# avr_programming_shield_v2b.net
KiCad netlist of a schematic drawn in EAGLE
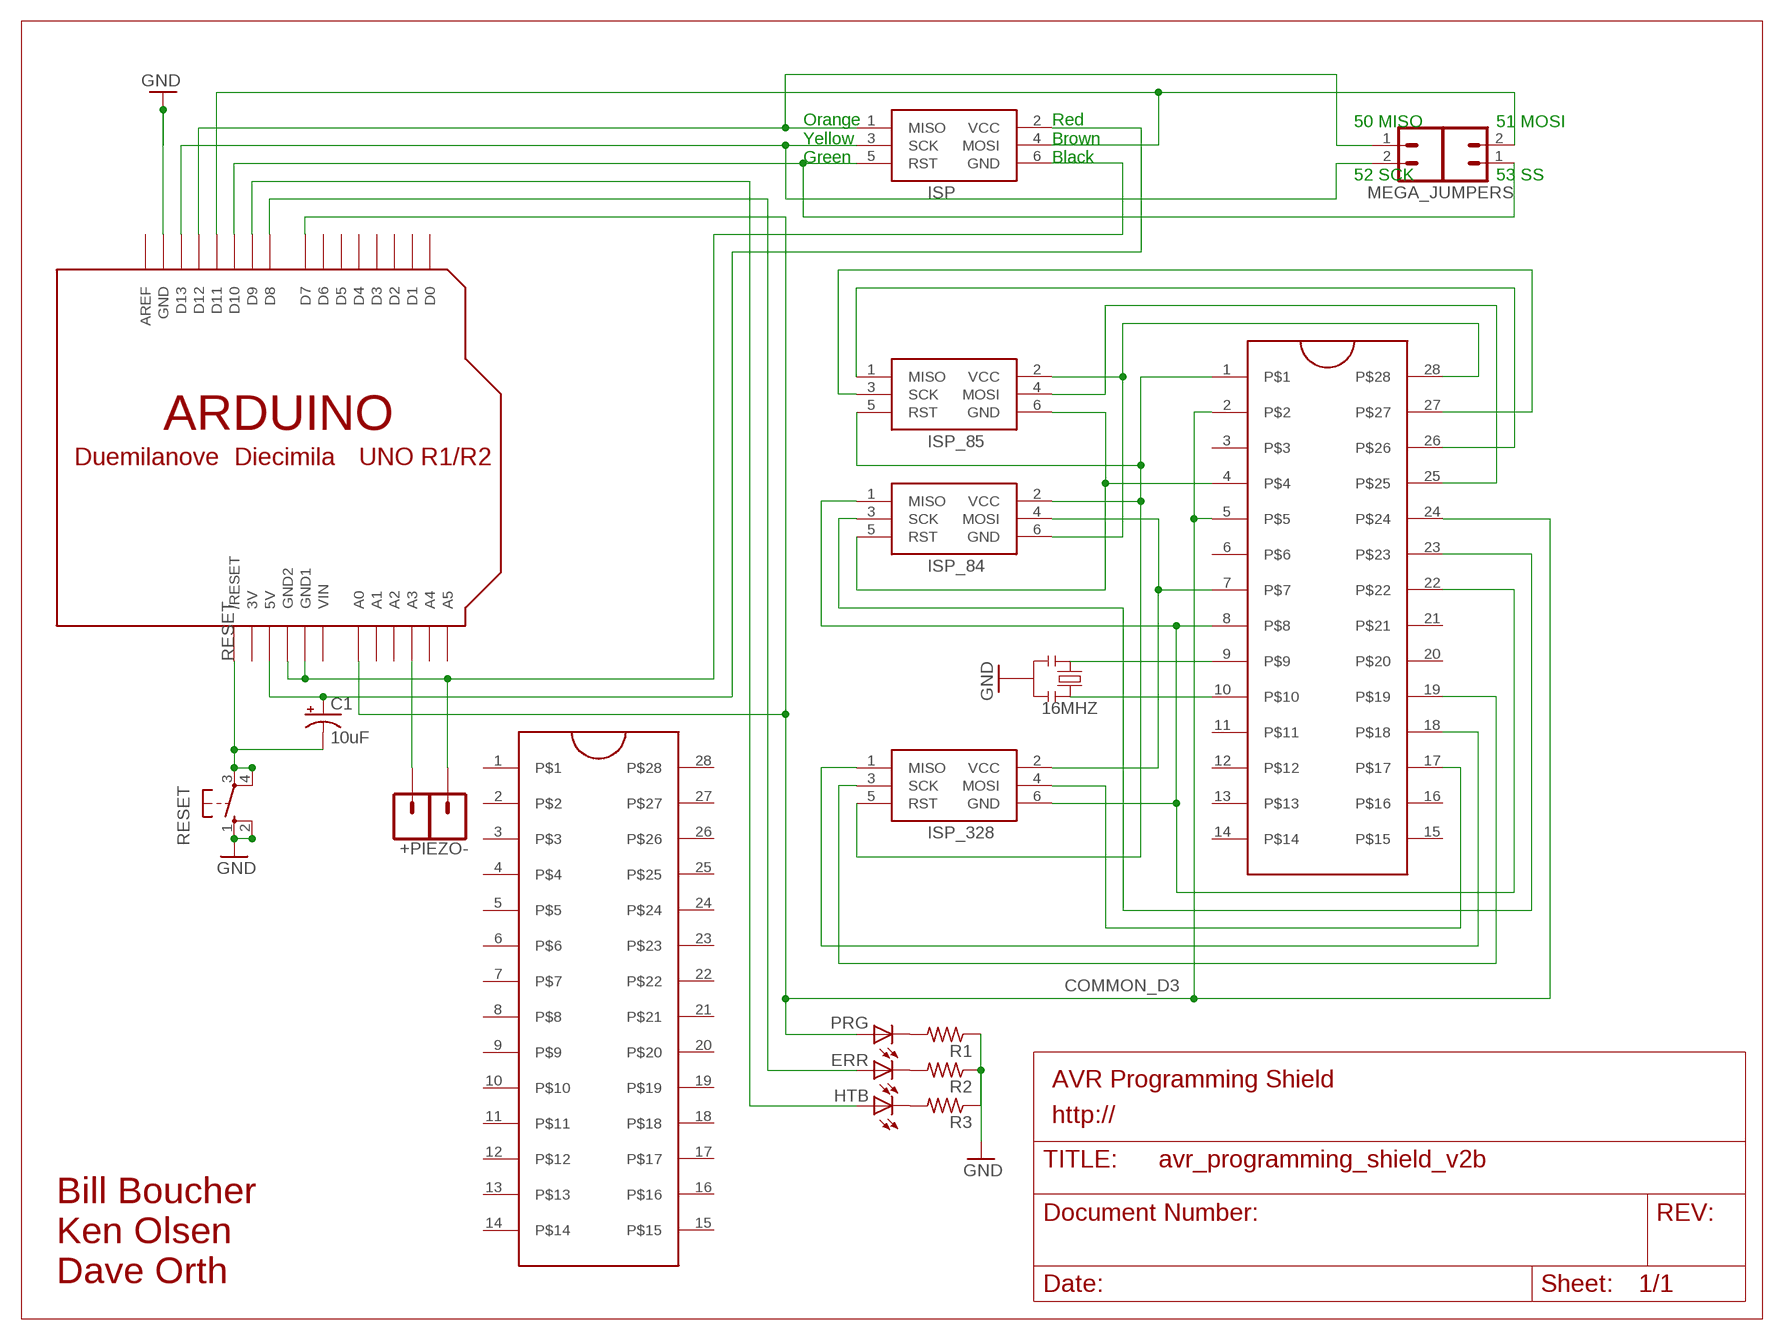
[diagram p0: schematic, sheet 1]

(export (version "E")
  (design (tool "Eeschema 10.0.6"))
  (components
    (comp (ref "+PIEZO-")
      (value "M01PTH")
      (footprint "eagle-import:1X01")
      (libsource (lib "eagle-import") (part "M01PTH"))
    )
    (comp (ref "16MHZ")
      (value "RESONATORPTH")
      (footprint "eagle-import:RESONATOR-PTH")
      (libsource (lib "eagle-import") (part "RESONATORPTH"))
    )
    (comp (ref "C1")
      (value "10uF")
      (footprint "eagle-import:CPOL-RADIAL-10UF-25V")
      (fields (field (name "MF") "ILLINOIS CAPACITOR,INC.") (field (name "MPN") "106TTA035M"))
      (libsource (lib "eagle-import") (part "CAP_POLPTH2"))
    )
    (comp (ref "ERR")
      (value "LED3MM")
      (footprint "eagle-import:LED3MM")
      (libsource (lib "eagle-import") (part "LED3MM"))
    )
    (comp (ref "HTB")
      (value "LED3MM")
      (footprint "eagle-import:LED3MM")
      (libsource (lib "eagle-import") (part "LED3MM"))
    )
    (comp (ref "ISP")
      (value "AVRISP-6")
      (footprint "eagle-import:AVRISP")
      (libsource (lib "eagle-import") (part "AVRISP-6"))
    )
    (comp (ref "ISP_84")
      (value "AVRISP-6")
      (footprint "eagle-import:AVRISP")
      (libsource (lib "eagle-import") (part "AVRISP-6"))
    )
    (comp (ref "ISP_85")
      (value "AVRISP-6")
      (footprint "eagle-import:AVRISP")
      (libsource (lib "eagle-import") (part "AVRISP-6"))
    )
    (comp (ref "ISP_328")
      (value "AVRISP-6")
      (footprint "eagle-import:AVRISP")
      (libsource (lib "eagle-import") (part "AVRISP-6"))
    )
    (comp (ref "JP2")
      (value "M02PTH")
      (footprint "eagle-import:1X02")
      (libsource (lib "eagle-import") (part "M02PTH"))
    )
    (comp (ref "JP4")
      (value "M01PTH")
      (footprint "eagle-import:1X01")
      (libsource (lib "eagle-import") (part "M01PTH"))
    )
    (comp (ref "MEGA_JUMPERS")
      (value "M02PTH")
      (footprint "eagle-import:1X02")
      (libsource (lib "eagle-import") (part "M02PTH"))
    )
    (comp (ref "PRG")
      (value "LED3MM")
      (footprint "eagle-import:LED3MM")
      (libsource (lib "eagle-import") (part "LED3MM"))
    )
    (comp (ref "R1")
      (value "R-US_0204/2V")
      (footprint "eagle-import:0204V")
      (libsource (lib "eagle-import") (part "R-US_0204/2V"))
    )
    (comp (ref "R2")
      (value "R-US_0204/2V")
      (footprint "eagle-import:0204V")
      (libsource (lib "eagle-import") (part "R-US_0204/2V"))
    )
    (comp (ref "R3")
      (value "R-US_0204/2V")
      (footprint "eagle-import:0204V")
      (libsource (lib "eagle-import") (part "R-US_0204/2V"))
    )
    (comp (ref "RESET")
      (value "10-XX")
      (footprint "eagle-import:B3F-10XX")
      (fields
        (field (name "MPN") "B3F-1000")
        (field (name "MPN_1") "B3F-1000")
        (field (name "OC_NEWARK") "36M3542")
      )
      (libsource (lib "eagle-import") (part "10-XX"))
    )
    (comp (ref "U$3")
      (value "ZIFSOCKET-28-3ZIFFSOCKET-28-3")
      (footprint "eagle-import:DIL28-3-ZIF_SOCKET")
      (libsource (lib "eagle-import") (part "ZIFSOCKET-28-3ZIFFSOCKET-28-3"))
    )
    (comp (ref "U$4")
      (value "ZIFSOCKET-28-3ZIFFSOCKET-28-3")
      (footprint "eagle-import:DIL28-3-ZIF_SOCKET")
      (libsource (lib "eagle-import") (part "SparkFun_mod_ZIFSOCKET-28-3ZIFFSOCKET-28-3"))
    )
    (comp (ref "U$5")
      (value "ARDUINO-NOHOLE")
      (footprint "eagle-import:ARDUINO-NOHOLE")
      (libsource (lib "eagle-import") (part "ARDUINO-NOHOLE"))
    )
  )
  (nets
    (net (code "1") (name "/3V") (class "Default")
      (node (ref "U$5") (pin "3V") (pinfunction "3V_3V") (pintype "power_in"))
    )
    (net (code "2") (name "/COMMON_D3") (class "Default")
      (node (ref "PRG") (pin "A") (pinfunction "A_A") (pintype "passive"))
      (node (ref "U$4") (pin "2") (pinfunction "P$2_2") (pintype "bidirectional"))
      (node (ref "U$4") (pin "24") (pinfunction "P$24_24") (pintype "bidirectional"))
      (node (ref "U$4") (pin "5") (pinfunction "P$5_5") (pintype "bidirectional"))
      (node (ref "U$5") (pin "A0") (pinfunction "A0_A0") (pintype "bidirectional"))
      (node (ref "U$5") (pin "D7") (pinfunction "D7_D7") (pintype "bidirectional"))
    )
    (net (code "3") (name "/RESET") (class "Default")
      (node (ref "C1") (pin "2") (pinfunction "-_2") (pintype "passive"))
      (node (ref "RESET") (pin "3") (pinfunction "P_3") (pintype "passive"))
      (node (ref "RESET") (pin "4") (pinfunction "P1_4") (pintype "passive"))
      (node (ref "U$5") (pin "RESET") (pinfunction "/RESET_RESET") (pintype "bidirectional"))
    )
    (net (code "4") (name "/VIN") (class "Default")
      (node (ref "U$5") (pin "VIN") (pinfunction "VIN_VIN") (pintype "power_in"))
    )
    (net (code "5") (name "GND") (class "Default")
      (node (ref "+PIEZO-") (pin "1") (pinfunction "1_1") (pintype "passive"))
      (node (ref "16MHZ") (pin "2") (pinfunction "2_2") (pintype "passive"))
      (node (ref "ISP") (pin "6") (pinfunction "GND_6") (pintype "power_in"))
      (node (ref "R1") (pin "1") (pinfunction "1_1") (pintype "passive"))
      (node (ref "R2") (pin "1") (pinfunction "1_1") (pintype "passive"))
      (node (ref "R3") (pin "1") (pinfunction "1_1") (pintype "passive"))
      (node (ref "RESET") (pin "1") (pinfunction "S_1") (pintype "passive"))
      (node (ref "RESET") (pin "2") (pinfunction "S1_2") (pintype "passive"))
      (node (ref "U$5") (pin "GND") (pinfunction "GND_GND") (pintype "power_in"))
      (node (ref "U$5") (pin "GND1") (pinfunction "GND1_GND1") (pintype "power_in"))
      (node (ref "U$5") (pin "GND2") (pinfunction "GND2_GND2") (pintype "power_in"))
    )
    (net (code "6") (name "Net-(C1-+)") (class "Default")
      (node (ref "C1") (pin "1") (pinfunction "+_1") (pintype "passive"))
      (node (ref "ISP") (pin "2") (pinfunction "VCC_2") (pintype "power_in"))
      (node (ref "U$5") (pin "5V") (pinfunction "5V_5V") (pintype "power_in"))
    )
    (net (code "7") (name "Net-(ERR-C)") (class "Default")
      (node (ref "ERR") (pin "K") (pinfunction "C_K") (pintype "passive"))
      (node (ref "R2") (pin "2") (pinfunction "2_2") (pintype "passive"))
    )
    (net (code "8") (name "Net-(ERR-PadA)") (class "Default")
      (node (ref "ERR") (pin "A") (pinfunction "A_A") (pintype "passive"))
      (node (ref "U$5") (pin "D8") (pinfunction "D8_D8") (pintype "bidirectional"))
    )
    (net (code "9") (name "Net-(HTB-C)") (class "Default")
      (node (ref "HTB") (pin "K") (pinfunction "C_K") (pintype "passive"))
      (node (ref "R3") (pin "2") (pinfunction "2_2") (pintype "passive"))
    )
    (net (code "10") (name "Net-(HTB-PadA)") (class "Default")
      (node (ref "HTB") (pin "A") (pinfunction "A_A") (pintype "passive"))
      (node (ref "U$5") (pin "D9") (pinfunction "D9_D9") (pintype "bidirectional"))
    )
    (net (code "11") (name "Net-(ISP-MISO)") (class "Default")
      (node (ref "ISP") (pin "1") (pinfunction "MISO_1") (pintype "input"))
      (node (ref "MEGA_JUMPERS") (pin "1") (pinfunction "1_1") (pintype "passive"))
      (node (ref "U$5") (pin "D12") (pinfunction "D12_D12") (pintype "bidirectional"))
    )
    (net (code "12") (name "Net-(ISP-MOSI)") (class "Default")
      (node (ref "ISP") (pin "4") (pinfunction "MOSI_4") (pintype "output"))
      (node (ref "JP2") (pin "2") (pinfunction "2_2") (pintype "passive"))
      (node (ref "U$5") (pin "D11") (pinfunction "D11_D11") (pintype "bidirectional"))
    )
    (net (code "13") (name "Net-(ISP-RST)") (class "Default")
      (node (ref "ISP") (pin "5") (pinfunction "RST_5") (pintype "output"))
      (node (ref "JP2") (pin "1") (pinfunction "1_1") (pintype "passive"))
      (node (ref "U$5") (pin "D10") (pinfunction "D10_D10") (pintype "bidirectional"))
    )
    (net (code "14") (name "Net-(ISP-SCK)") (class "Default")
      (node (ref "ISP") (pin "3") (pinfunction "SCK_3") (pintype "output"))
      (node (ref "MEGA_JUMPERS") (pin "2") (pinfunction "2_2") (pintype "passive"))
      (node (ref "U$5") (pin "D13") (pinfunction "D13_D13") (pintype "bidirectional"))
    )
    (net (code "15") (name "Net-(ISP_84-GND)") (class "Default")
      (node (ref "ISP_84") (pin "6") (pinfunction "GND_6") (pintype "power_in"))
      (node (ref "ISP_85") (pin "2") (pinfunction "VCC_2") (pintype "power_in"))
      (node (ref "U$4") (pin "28") (pinfunction "P$28_28") (pintype "bidirectional"))
    )
    (net (code "16") (name "Net-(ISP_84-RST)") (class "Default")
      (node (ref "ISP_84") (pin "5") (pinfunction "RST_5") (pintype "output"))
      (node (ref "ISP_85") (pin "6") (pinfunction "GND_6") (pintype "power_in"))
      (node (ref "U$4") (pin "4") (pinfunction "P$4_4") (pintype "bidirectional"))
    )
    (net (code "17") (name "Net-(ISP_84-SCK)") (class "Default")
      (node (ref "ISP_84") (pin "3") (pinfunction "SCK_3") (pintype "output"))
      (node (ref "U$4") (pin "23") (pinfunction "P$23_23") (pintype "bidirectional"))
    )
    (net (code "18") (name "Net-(ISP_85-MISO)") (class "Default")
      (node (ref "ISP_85") (pin "1") (pinfunction "MISO_1") (pintype "input"))
      (node (ref "U$4") (pin "26") (pinfunction "P$26_26") (pintype "bidirectional"))
    )
    (net (code "19") (name "Net-(ISP_85-MOSI)") (class "Default")
      (node (ref "ISP_85") (pin "4") (pinfunction "MOSI_4") (pintype "output"))
      (node (ref "U$4") (pin "25") (pinfunction "P$25_25") (pintype "bidirectional"))
    )
    (net (code "20") (name "Net-(ISP_85-SCK)") (class "Default")
      (node (ref "ISP_85") (pin "3") (pinfunction "SCK_3") (pintype "output"))
      (node (ref "U$4") (pin "27") (pinfunction "P$27_27") (pintype "bidirectional"))
    )
    (net (code "21") (name "Net-(ISP_328-GND)") (class "Default")
      (node (ref "ISP_328") (pin "6") (pinfunction "GND_6") (pintype "power_in"))
      (node (ref "ISP_84") (pin "1") (pinfunction "MISO_1") (pintype "input"))
      (node (ref "U$4") (pin "22") (pinfunction "P$22_22") (pintype "bidirectional"))
      (node (ref "U$4") (pin "8") (pinfunction "P$8_8") (pintype "bidirectional"))
    )
    (net (code "22") (name "Net-(ISP_328-MISO)") (class "Default")
      (node (ref "ISP_328") (pin "1") (pinfunction "MISO_1") (pintype "input"))
      (node (ref "U$4") (pin "18") (pinfunction "P$18_18") (pintype "bidirectional"))
    )
    (net (code "23") (name "Net-(ISP_328-MOSI)") (class "Default")
      (node (ref "ISP_328") (pin "4") (pinfunction "MOSI_4") (pintype "output"))
      (node (ref "U$4") (pin "17") (pinfunction "P$17_17") (pintype "bidirectional"))
    )
    (net (code "24") (name "Net-(ISP_328-RST)") (class "Default")
      (node (ref "ISP_328") (pin "5") (pinfunction "RST_5") (pintype "output"))
      (node (ref "ISP_84") (pin "2") (pinfunction "VCC_2") (pintype "power_in"))
      (node (ref "ISP_85") (pin "5") (pinfunction "RST_5") (pintype "output"))
      (node (ref "U$4") (pin "1") (pinfunction "P$1_1") (pintype "bidirectional"))
    )
    (net (code "25") (name "Net-(ISP_328-SCK)") (class "Default")
      (node (ref "ISP_328") (pin "3") (pinfunction "SCK_3") (pintype "output"))
      (node (ref "U$4") (pin "19") (pinfunction "P$19_19") (pintype "bidirectional"))
    )
    (net (code "26") (name "Net-(ISP_328-VCC)") (class "Default")
      (node (ref "ISP_328") (pin "2") (pinfunction "VCC_2") (pintype "power_in"))
      (node (ref "ISP_84") (pin "4") (pinfunction "MOSI_4") (pintype "output"))
      (node (ref "U$4") (pin "7") (pinfunction "P$7_7") (pintype "bidirectional"))
    )
    (net (code "27") (name "Net-(JP4-Pad1)") (class "Default")
      (node (ref "JP4") (pin "1") (pinfunction "1_1") (pintype "passive"))
      (node (ref "U$5") (pin "A3") (pinfunction "A3_A3") (pintype "bidirectional"))
    )
    (net (code "28") (name "Net-(PRG-C)") (class "Default")
      (node (ref "PRG") (pin "K") (pinfunction "C_K") (pintype "passive"))
      (node (ref "R1") (pin "2") (pinfunction "2_2") (pintype "passive"))
    )
    (net (code "29") (name "Net-(U$4-P$9)") (class "Default")
      (node (ref "16MHZ") (pin "1") (pinfunction "1_1") (pintype "passive"))
      (node (ref "U$4") (pin "9") (pinfunction "P$9_9") (pintype "bidirectional"))
    )
    (net (code "30") (name "Net-(U$4-P$10)") (class "Default")
      (node (ref "16MHZ") (pin "3") (pinfunction "3_3") (pintype "passive"))
      (node (ref "U$4") (pin "10") (pinfunction "P$10_10") (pintype "bidirectional"))
    )
    (net (code "31") (name "unconnected-(U$3-P$1-Pad1)") (class "Default")
      (node (ref "U$3") (pin "1") (pinfunction "P$1_1") (pintype "bidirectional"))
    )
    (net (code "32") (name "unconnected-(U$3-P$2-Pad2)") (class "Default")
      (node (ref "U$3") (pin "2") (pinfunction "P$2_2") (pintype "bidirectional"))
    )
    (net (code "33") (name "unconnected-(U$3-P$3-Pad3)") (class "Default")
      (node (ref "U$3") (pin "3") (pinfunction "P$3_3") (pintype "bidirectional"))
    )
    (net (code "34") (name "unconnected-(U$3-P$4-Pad4)") (class "Default")
      (node (ref "U$3") (pin "4") (pinfunction "P$4_4") (pintype "bidirectional"))
    )
    (net (code "35") (name "unconnected-(U$3-P$5-Pad5)") (class "Default")
      (node (ref "U$3") (pin "5") (pinfunction "P$5_5") (pintype "bidirectional"))
    )
    (net (code "36") (name "unconnected-(U$3-P$6-Pad6)") (class "Default")
      (node (ref "U$3") (pin "6") (pinfunction "P$6_6") (pintype "bidirectional"))
    )
    (net (code "37") (name "unconnected-(U$3-P$7-Pad7)") (class "Default")
      (node (ref "U$3") (pin "7") (pinfunction "P$7_7") (pintype "bidirectional"))
    )
    (net (code "38") (name "unconnected-(U$3-P$8-Pad8)") (class "Default")
      (node (ref "U$3") (pin "8") (pinfunction "P$8_8") (pintype "bidirectional"))
    )
    (net (code "39") (name "unconnected-(U$3-P$9-Pad9)") (class "Default")
      (node (ref "U$3") (pin "9") (pinfunction "P$9_9") (pintype "bidirectional"))
    )
    (net (code "40") (name "unconnected-(U$3-P$10-Pad10)") (class "Default")
      (node (ref "U$3") (pin "10") (pinfunction "P$10_10") (pintype "bidirectional"))
    )
    (net (code "41") (name "unconnected-(U$3-P$11-Pad11)") (class "Default")
      (node (ref "U$3") (pin "11") (pinfunction "P$11_11") (pintype "bidirectional"))
    )
    (net (code "42") (name "unconnected-(U$3-P$12-Pad12)") (class "Default")
      (node (ref "U$3") (pin "12") (pinfunction "P$12_12") (pintype "bidirectional"))
    )
    (net (code "43") (name "unconnected-(U$3-P$13-Pad13)") (class "Default")
      (node (ref "U$3") (pin "13") (pinfunction "P$13_13") (pintype "bidirectional"))
    )
    (net (code "44") (name "unconnected-(U$3-P$14-Pad14)") (class "Default")
      (node (ref "U$3") (pin "14") (pinfunction "P$14_14") (pintype "bidirectional"))
    )
    (net (code "45") (name "unconnected-(U$3-P$15-Pad15)") (class "Default")
      (node (ref "U$3") (pin "15") (pinfunction "P$15_15") (pintype "bidirectional"))
    )
    (net (code "46") (name "unconnected-(U$3-P$16-Pad16)") (class "Default")
      (node (ref "U$3") (pin "16") (pinfunction "P$16_16") (pintype "bidirectional"))
    )
    (net (code "47") (name "unconnected-(U$3-P$17-Pad17)") (class "Default")
      (node (ref "U$3") (pin "17") (pinfunction "P$17_17") (pintype "bidirectional"))
    )
    (net (code "48") (name "unconnected-(U$3-P$18-Pad18)") (class "Default")
      (node (ref "U$3") (pin "18") (pinfunction "P$18_18") (pintype "bidirectional"))
    )
    (net (code "49") (name "unconnected-(U$3-P$19-Pad19)") (class "Default")
      (node (ref "U$3") (pin "19") (pinfunction "P$19_19") (pintype "bidirectional"))
    )
    (net (code "50") (name "unconnected-(U$3-P$20-Pad20)") (class "Default")
      (node (ref "U$3") (pin "20") (pinfunction "P$20_20") (pintype "bidirectional"))
    )
    (net (code "51") (name "unconnected-(U$3-P$21-Pad21)") (class "Default")
      (node (ref "U$3") (pin "21") (pinfunction "P$21_21") (pintype "bidirectional"))
    )
    (net (code "52") (name "unconnected-(U$3-P$22-Pad22)") (class "Default")
      (node (ref "U$3") (pin "22") (pinfunction "P$22_22") (pintype "bidirectional"))
    )
    (net (code "53") (name "unconnected-(U$3-P$23-Pad23)") (class "Default")
      (node (ref "U$3") (pin "23") (pinfunction "P$23_23") (pintype "bidirectional"))
    )
    (net (code "54") (name "unconnected-(U$3-P$24-Pad24)") (class "Default")
      (node (ref "U$3") (pin "24") (pinfunction "P$24_24") (pintype "bidirectional"))
    )
    (net (code "55") (name "unconnected-(U$3-P$25-Pad25)") (class "Default")
      (node (ref "U$3") (pin "25") (pinfunction "P$25_25") (pintype "bidirectional"))
    )
    (net (code "56") (name "unconnected-(U$3-P$26-Pad26)") (class "Default")
      (node (ref "U$3") (pin "26") (pinfunction "P$26_26") (pintype "bidirectional"))
    )
    (net (code "57") (name "unconnected-(U$3-P$27-Pad27)") (class "Default")
      (node (ref "U$3") (pin "27") (pinfunction "P$27_27") (pintype "bidirectional"))
    )
    (net (code "58") (name "unconnected-(U$3-P$28-Pad28)") (class "Default")
      (node (ref "U$3") (pin "28") (pinfunction "P$28_28") (pintype "bidirectional"))
    )
    (net (code "59") (name "unconnected-(U$4-P$3-Pad3)") (class "Default")
      (node (ref "U$4") (pin "3") (pinfunction "P$3_3") (pintype "bidirectional"))
    )
    (net (code "60") (name "unconnected-(U$4-P$6-Pad6)") (class "Default")
      (node (ref "U$4") (pin "6") (pinfunction "P$6_6") (pintype "bidirectional"))
    )
    (net (code "61") (name "unconnected-(U$4-P$11-Pad11)") (class "Default")
      (node (ref "U$4") (pin "11") (pinfunction "P$11_11") (pintype "bidirectional"))
    )
    (net (code "62") (name "unconnected-(U$4-P$12-Pad12)") (class "Default")
      (node (ref "U$4") (pin "12") (pinfunction "P$12_12") (pintype "bidirectional"))
    )
    (net (code "63") (name "unconnected-(U$4-P$13-Pad13)") (class "Default")
      (node (ref "U$4") (pin "13") (pinfunction "P$13_13") (pintype "bidirectional"))
    )
    (net (code "64") (name "unconnected-(U$4-P$14-Pad14)") (class "Default")
      (node (ref "U$4") (pin "14") (pinfunction "P$14_14") (pintype "bidirectional"))
    )
    (net (code "65") (name "unconnected-(U$4-P$15-Pad15)") (class "Default")
      (node (ref "U$4") (pin "15") (pinfunction "P$15_15") (pintype "bidirectional"))
    )
    (net (code "66") (name "unconnected-(U$4-P$16-Pad16)") (class "Default")
      (node (ref "U$4") (pin "16") (pinfunction "P$16_16") (pintype "bidirectional"))
    )
    (net (code "67") (name "unconnected-(U$4-P$20-Pad20)") (class "Default")
      (node (ref "U$4") (pin "20") (pinfunction "P$20_20") (pintype "bidirectional"))
    )
    (net (code "68") (name "unconnected-(U$4-P$21-Pad21)") (class "Default")
      (node (ref "U$4") (pin "21") (pinfunction "P$21_21") (pintype "bidirectional"))
    )
    (net (code "69") (name "unconnected-(U$5-PadA1)") (class "Default")
      (node (ref "U$5") (pin "A1") (pinfunction "A1_A1") (pintype "bidirectional"))
    )
    (net (code "70") (name "unconnected-(U$5-PadA2)") (class "Default")
      (node (ref "U$5") (pin "A2") (pinfunction "A2_A2") (pintype "bidirectional"))
    )
    (net (code "71") (name "unconnected-(U$5-PadA4)") (class "Default")
      (node (ref "U$5") (pin "A4") (pinfunction "A4_A4") (pintype "bidirectional"))
    )
    (net (code "72") (name "unconnected-(U$5-PadA5)") (class "Default")
      (node (ref "U$5") (pin "A5") (pinfunction "A5_A5") (pintype "bidirectional"))
    )
    (net (code "73") (name "unconnected-(U$5-PadAREF)") (class "Default")
      (node (ref "U$5") (pin "AREF") (pinfunction "AREF_AREF") (pintype "bidirectional"))
    )
    (net (code "74") (name "unconnected-(U$5-PadD0)") (class "Default")
      (node (ref "U$5") (pin "D0") (pinfunction "D0_D0") (pintype "bidirectional"))
    )
    (net (code "75") (name "unconnected-(U$5-PadD1)") (class "Default")
      (node (ref "U$5") (pin "D1") (pinfunction "D1_D1") (pintype "bidirectional"))
    )
    (net (code "76") (name "unconnected-(U$5-PadD2)") (class "Default")
      (node (ref "U$5") (pin "D2") (pinfunction "D2_D2") (pintype "bidirectional"))
    )
    (net (code "77") (name "unconnected-(U$5-PadD3)") (class "Default")
      (node (ref "U$5") (pin "D3") (pinfunction "D3_D3") (pintype "bidirectional"))
    )
    (net (code "78") (name "unconnected-(U$5-PadD4)") (class "Default")
      (node (ref "U$5") (pin "D4") (pinfunction "D4_D4") (pintype "bidirectional"))
    )
    (net (code "79") (name "unconnected-(U$5-PadD5)") (class "Default")
      (node (ref "U$5") (pin "D5") (pinfunction "D5_D5") (pintype "bidirectional"))
    )
    (net (code "80") (name "unconnected-(U$5-PadD6)") (class "Default")
      (node (ref "U$5") (pin "D6") (pinfunction "D6_D6") (pintype "bidirectional"))
    )
  )
)
